# 1uO_c_v_1_2.net
KiCad netlist of a schematic drawn in EAGLE
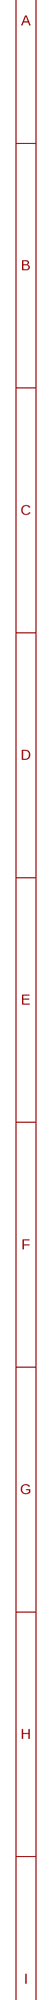
[diagram p0: schematic, sheet 1, part 1 of 2]
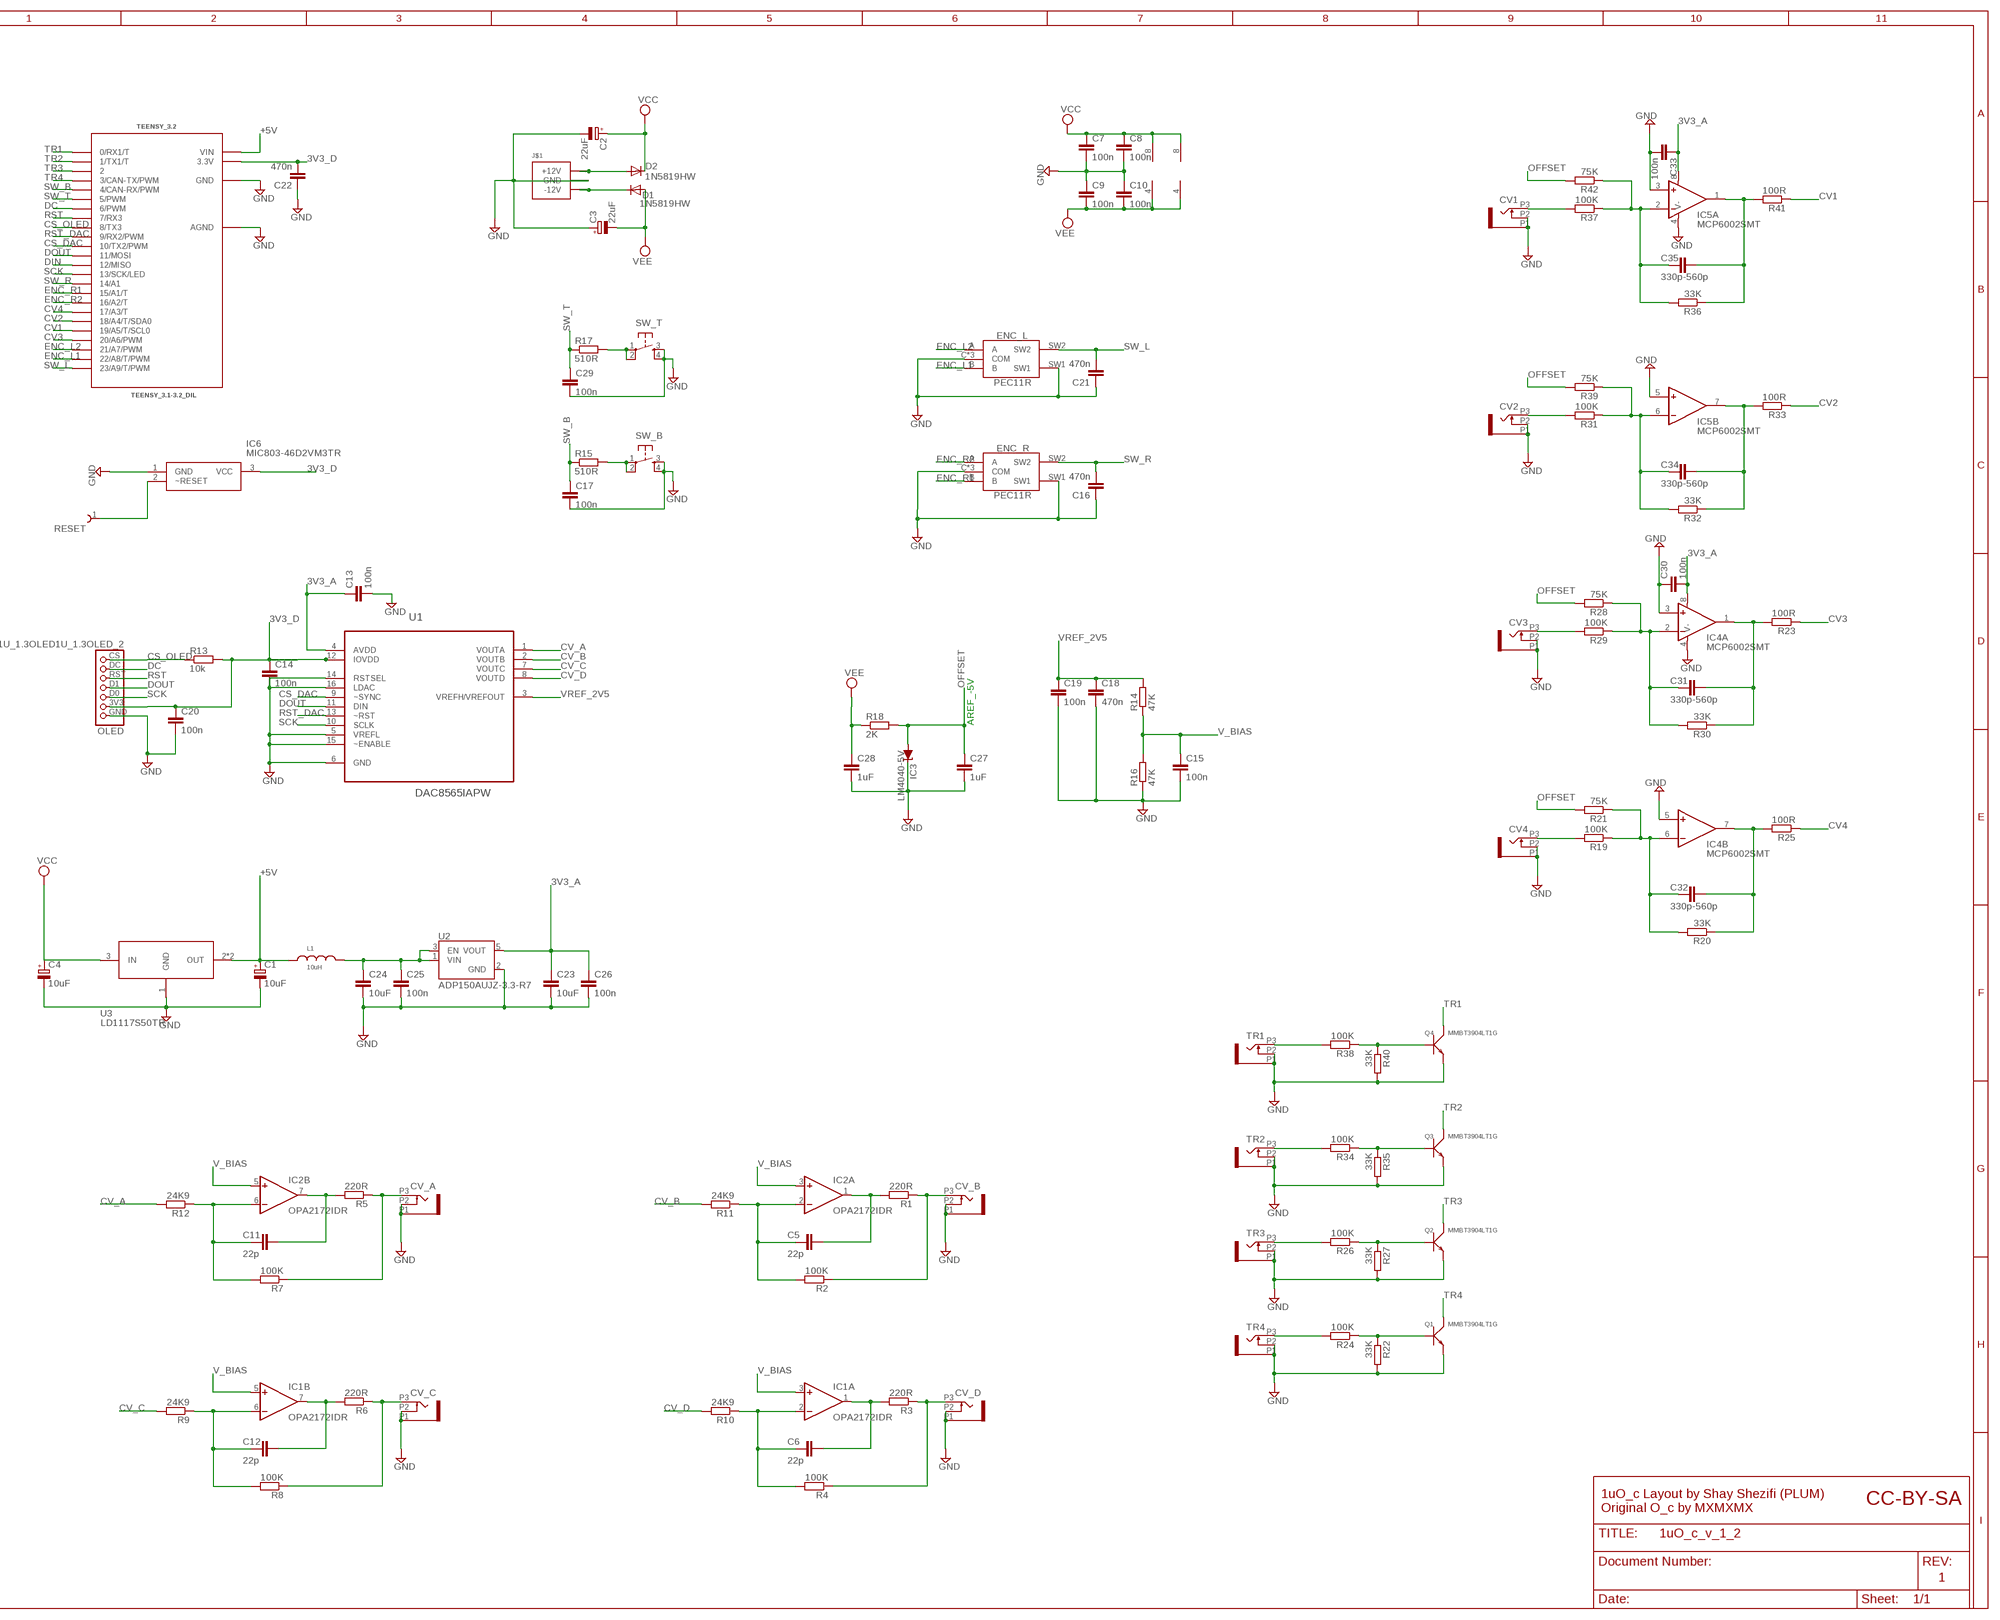
[diagram p1: schematic, sheet 1, part 2 of 2]

(export (version "E")
  (design (tool "Eeschema 10.0.6"))
  (components
    (comp (ref "C1")
      (value "10uF")
      (footprint "eagle-import:PANASONIC_B")
      (libsource (lib "eagle-import") (part "CPOL-EUB"))
    )
    (comp (ref "C2")
      (value "22uF")
      (footprint "eagle-import:PANASONIC_C")
      (libsource (lib "eagle-import") (part "CPOL-EUC"))
    )
    (comp (ref "C3")
      (value "22uF")
      (footprint "eagle-import:PANASONIC_C")
      (libsource (lib "eagle-import") (part "CPOL-EUC"))
    )
    (comp (ref "C4")
      (value "10uF")
      (footprint "eagle-import:PANASONIC_B")
      (libsource (lib "eagle-import") (part "CPOL-EUB"))
    )
    (comp (ref "C5")
      (value "22p")
      (footprint "eagle-import:C0603")
      (libsource (lib "eagle-import") (part "C-EUC0603"))
    )
    (comp (ref "C6")
      (value "22p")
      (footprint "eagle-import:C0603")
      (libsource (lib "eagle-import") (part "C-EUC0603"))
    )
    (comp (ref "C7")
      (value "100n")
      (footprint "eagle-import:C0603")
      (libsource (lib "eagle-import") (part "C-EUC0603"))
    )
    (comp (ref "C8")
      (value "100n")
      (footprint "eagle-import:C0603")
      (libsource (lib "eagle-import") (part "C-EUC0603"))
    )
    (comp (ref "C9")
      (value "100n")
      (footprint "eagle-import:C0603")
      (libsource (lib "eagle-import") (part "C-EUC0603"))
    )
    (comp (ref "C10")
      (value "100n")
      (footprint "eagle-import:C0603")
      (libsource (lib "eagle-import") (part "C-EUC0603"))
    )
    (comp (ref "C11")
      (value "22p")
      (footprint "eagle-import:C0603")
      (libsource (lib "eagle-import") (part "C-EUC0603"))
    )
    (comp (ref "C12")
      (value "22p")
      (footprint "eagle-import:C0603")
      (libsource (lib "eagle-import") (part "C-EUC0603"))
    )
    (comp (ref "C13")
      (value "100n")
      (footprint "eagle-import:C0603")
      (libsource (lib "eagle-import") (part "C-EUC0603"))
    )
    (comp (ref "C14")
      (value "100n")
      (footprint "eagle-import:C0603")
      (libsource (lib "eagle-import") (part "C-EUC0603"))
    )
    (comp (ref "C15")
      (value "100n")
      (footprint "eagle-import:C0603")
      (libsource (lib "eagle-import") (part "C-EUC0603"))
    )
    (comp (ref "C16")
      (value "470n")
      (footprint "eagle-import:C0603")
      (libsource (lib "eagle-import") (part "C-EUC0603"))
    )
    (comp (ref "C17")
      (value "100n")
      (footprint "eagle-import:C0603")
      (libsource (lib "eagle-import") (part "C-EUC0603"))
    )
    (comp (ref "C18")
      (value "470n")
      (footprint "eagle-import:C0603")
      (libsource (lib "eagle-import") (part "C-EUC0603"))
    )
    (comp (ref "C19")
      (value "100n")
      (footprint "eagle-import:C0603")
      (libsource (lib "eagle-import") (part "C-EUC0603"))
    )
    (comp (ref "C20")
      (value "100n")
      (footprint "eagle-import:C0603")
      (libsource (lib "eagle-import") (part "C-EUC0603"))
    )
    (comp (ref "C21")
      (value "470n")
      (footprint "eagle-import:C0603")
      (libsource (lib "eagle-import") (part "C-EUC0603"))
    )
    (comp (ref "C22")
      (value "470n")
      (footprint "eagle-import:C0603")
      (libsource (lib "eagle-import") (part "C-EUC0603"))
    )
    (comp (ref "C23")
      (value "10uF")
      (footprint "eagle-import:C1206K")
      (libsource (lib "eagle-import") (part "C-EUC1206K"))
    )
    (comp (ref "C24")
      (value "10uF")
      (footprint "eagle-import:C1206K")
      (libsource (lib "eagle-import") (part "C-EUC1206K"))
    )
    (comp (ref "C25")
      (value "100n")
      (footprint "eagle-import:C0603")
      (libsource (lib "eagle-import") (part "C-EUC0603"))
    )
    (comp (ref "C26")
      (value "100n")
      (footprint "eagle-import:C0603")
      (libsource (lib "eagle-import") (part "C-EUC0603"))
    )
    (comp (ref "C27")
      (value "1uF")
      (footprint "eagle-import:C0603")
      (libsource (lib "eagle-import") (part "C-EUC0603"))
    )
    (comp (ref "C28")
      (value "1uF")
      (footprint "eagle-import:C0603")
      (libsource (lib "eagle-import") (part "C-EUC0603"))
    )
    (comp (ref "C29")
      (value "100n")
      (footprint "eagle-import:C0603")
      (libsource (lib "eagle-import") (part "C-EUC0603"))
    )
    (comp (ref "C30")
      (value "100n")
      (footprint "eagle-import:C0603")
      (libsource (lib "eagle-import") (part "C-EUC0603"))
    )
    (comp (ref "C31")
      (value "330p-560p")
      (footprint "eagle-import:C0603")
      (libsource (lib "eagle-import") (part "C-EUC0603"))
    )
    (comp (ref "C32")
      (value "330p-560p")
      (footprint "eagle-import:C0603")
      (libsource (lib "eagle-import") (part "C-EUC0603"))
    )
    (comp (ref "C33")
      (value "100n")
      (footprint "eagle-import:C0603")
      (libsource (lib "eagle-import") (part "C-EUC0603"))
    )
    (comp (ref "C34")
      (value "330p-560p")
      (footprint "eagle-import:C0603")
      (libsource (lib "eagle-import") (part "C-EUC0603"))
    )
    (comp (ref "C35")
      (value "330p-560p")
      (footprint "eagle-import:C0603")
      (libsource (lib "eagle-import") (part "C-EUC0603"))
    )
    (comp (ref "CV1")
      (value "OG-PJ301_PJ301_THONKICONN")
      (footprint "eagle-import:OG-PJ301_WQP_PJ_301M6_NO_HOLE")
      (libsource (lib "eagle-import") (part "OG-PJ301_PJ301_THONKICONN"))
    )
    (comp (ref "CV2")
      (value "OG-PJ301_PJ301_THONKICONN")
      (footprint "eagle-import:OG-PJ301_WQP_PJ_301M6_NO_HOLE")
      (libsource (lib "eagle-import") (part "OG-PJ301_PJ301_THONKICONN"))
    )
    (comp (ref "CV3")
      (value "OG-PJ301_PJ301_THONKICONN")
      (footprint "eagle-import:OG-PJ301_WQP_PJ_301M6_NO_HOLE")
      (libsource (lib "eagle-import") (part "OG-PJ301_PJ301_THONKICONN"))
    )
    (comp (ref "CV4")
      (value "OG-PJ301_PJ301_THONKICONN")
      (footprint "eagle-import:OG-PJ301_WQP_PJ_301M6_NO_HOLE")
      (libsource (lib "eagle-import") (part "OG-PJ301_PJ301_THONKICONN"))
    )
    (comp (ref "CV_A")
      (value "OG-PJ301_PJ301_THONKICONN")
      (footprint "eagle-import:OG-PJ301_WQP_PJ_301M6_NO_HOLE")
      (libsource (lib "eagle-import") (part "OG-PJ301_PJ301_THONKICONN"))
    )
    (comp (ref "CV_B")
      (value "OG-PJ301_PJ301_THONKICONN")
      (footprint "eagle-import:OG-PJ301_WQP_PJ_301M6_NO_HOLE")
      (libsource (lib "eagle-import") (part "OG-PJ301_PJ301_THONKICONN"))
    )
    (comp (ref "CV_C")
      (value "OG-PJ301_PJ301_THONKICONN")
      (footprint "eagle-import:OG-PJ301_WQP_PJ_301M6_NO_HOLE")
      (libsource (lib "eagle-import") (part "OG-PJ301_PJ301_THONKICONN"))
    )
    (comp (ref "CV_D")
      (value "OG-PJ301_PJ301_THONKICONN")
      (footprint "eagle-import:OG-PJ301_WQP_PJ_301M6_NO_HOLE")
      (libsource (lib "eagle-import") (part "OG-PJ301_PJ301_THONKICONN"))
    )
    (comp (ref "D1")
      (value "1N5819HW")
      (footprint "eagle-import:DIODE_SOD123")
      (libsource (lib "eagle-import") (part "DIODE_DIODE-SOD123"))
    )
    (comp (ref "D2")
      (value "1N5819HW")
      (footprint "eagle-import:DIODE_SOD123")
      (libsource (lib "eagle-import") (part "DIODE_DIODE-SOD123"))
    )
    (comp (ref "ENC_L")
      (value "PEC11R")
      (footprint "eagle-import:PEC11R-4XXXK-SXXXX")
      (fields
        (field (name "ARROW_PART_NUMBER") "PEC11R-4215K-S0024")
        (field (name "RS_PART_NUMBER") "1674651")
      )
      (libsource (lib "eagle-import") (part "PEC11R"))
    )
    (comp (ref "ENC_R")
      (value "PEC11R")
      (footprint "eagle-import:PEC11R-4XXXK-SXXXX")
      (fields
        (field (name "ARROW_PART_NUMBER") "PEC11R-4215K-S0024")
        (field (name "RS_PART_NUMBER") "1674651")
      )
      (libsource (lib "eagle-import") (part "PEC11R"))
    )
    (comp (ref "IC1")
      (value "OPA2172IDR")
      (footprint "eagle-import:SO08")
      (libsource (lib "eagle-import") (part "TL072D"))
    )
    (comp (ref "IC2")
      (value "OPA2172IDR")
      (footprint "eagle-import:SO08")
      (libsource (lib "eagle-import") (part "TL072D"))
    )
    (comp (ref "IC3")
      (value "LM4040-5V")
      (footprint "eagle-import:DBZ_R-PDSO-G3")
      (libsource (lib "eagle-import") (part "LM4041DBZB12"))
    )
    (comp (ref "IC4")
      (value "MCP6002SMT")
      (footprint "eagle-import:SOIC8")
      (libsource (lib "eagle-import") (part "MCP6002SMT"))
    )
    (comp (ref "IC5")
      (value "MCP6002SMT")
      (footprint "eagle-import:SOIC8")
      (libsource (lib "eagle-import") (part "MCP6002SMT"))
    )
    (comp (ref "IC6")
      (value "MIC803-46D2VM3TR")
      (footprint "eagle-import:SOT95P230X110-3N")
      (libsource (lib "eagle-import") (part "MIC803-46D2VM3TR"))
    )
    (comp (ref "J$1")
      (value "POWER_SIMPLE10")
      (footprint "eagle-import:POWER_10")
      (libsource (lib "eagle-import") (part "POWER_SIMPLE10"))
    )
    (comp (ref "L1")
      (value "10uH")
      (footprint "eagle-import:WE-LQ_M")
      (libsource (lib "eagle-import") (part "WE-LQ_1210_744032001"))
    )
    (comp (ref "OLED")
      (value "1U_1.3OLED1U_1.3OLED_2")
      (footprint "eagle-import:1U_1.3OLED_2")
      (libsource (lib "eagle-import") (part "1U_1.3OLED1U_1.3OLED_2"))
    )
    (comp (ref "Q1")
      (value "MMBT3904LT1G")
      (footprint "eagle-import:SOT-23")
      (libsource (lib "eagle-import") (part "SMD-TRANSISTORS-NPN-40V-200MA-MMBT3904LT1G(SOT-23)"))
    )
    (comp (ref "Q2")
      (value "MMBT3904LT1G")
      (footprint "eagle-import:SOT-23")
      (libsource (lib "eagle-import") (part "SMD-TRANSISTORS-NPN-40V-200MA-MMBT3904LT1G(SOT-23)"))
    )
    (comp (ref "Q3")
      (value "MMBT3904LT1G")
      (footprint "eagle-import:SOT-23")
      (libsource (lib "eagle-import") (part "SMD-TRANSISTORS-NPN-40V-200MA-MMBT3904LT1G(SOT-23)"))
    )
    (comp (ref "Q4")
      (value "MMBT3904LT1G")
      (footprint "eagle-import:SOT-23")
      (libsource (lib "eagle-import") (part "SMD-TRANSISTORS-NPN-40V-200MA-MMBT3904LT1G(SOT-23)"))
    )
    (comp (ref "R1")
      (value "220R")
      (footprint "eagle-import:R0603")
      (libsource (lib "eagle-import") (part "R-EU_R0603"))
    )
    (comp (ref "R2")
      (value "100K")
      (footprint "eagle-import:R0603")
      (libsource (lib "eagle-import") (part "R-EU_R0603"))
    )
    (comp (ref "R3")
      (value "220R")
      (footprint "eagle-import:R0603")
      (libsource (lib "eagle-import") (part "R-EU_R0603"))
    )
    (comp (ref "R4")
      (value "100K")
      (footprint "eagle-import:R0603")
      (libsource (lib "eagle-import") (part "R-EU_R0603"))
    )
    (comp (ref "R5")
      (value "220R")
      (footprint "eagle-import:R0603")
      (libsource (lib "eagle-import") (part "R-EU_R0603"))
    )
    (comp (ref "R6")
      (value "220R")
      (footprint "eagle-import:R0603")
      (libsource (lib "eagle-import") (part "R-EU_R0603"))
    )
    (comp (ref "R7")
      (value "100K")
      (footprint "eagle-import:R0603")
      (libsource (lib "eagle-import") (part "R-EU_R0603"))
    )
    (comp (ref "R8")
      (value "100K")
      (footprint "eagle-import:R0603")
      (libsource (lib "eagle-import") (part "R-EU_R0603"))
    )
    (comp (ref "R9")
      (value "24K9")
      (footprint "eagle-import:R0603")
      (libsource (lib "eagle-import") (part "R-EU_R0603"))
    )
    (comp (ref "R10")
      (value "24K9")
      (footprint "eagle-import:R0603")
      (libsource (lib "eagle-import") (part "R-EU_R0603"))
    )
    (comp (ref "R11")
      (value "24K9")
      (footprint "eagle-import:R0603")
      (libsource (lib "eagle-import") (part "R-EU_R0603"))
    )
    (comp (ref "R12")
      (value "24K9")
      (footprint "eagle-import:R0603")
      (libsource (lib "eagle-import") (part "R-EU_R0603"))
    )
    (comp (ref "R13")
      (value "10k")
      (footprint "eagle-import:R0603")
      (libsource (lib "eagle-import") (part "R-EU_R0603"))
    )
    (comp (ref "R14")
      (value "47K")
      (footprint "eagle-import:R0603")
      (libsource (lib "eagle-import") (part "R-EU_R0603"))
    )
    (comp (ref "R15")
      (value "510R")
      (footprint "eagle-import:R0603")
      (libsource (lib "eagle-import") (part "R-EU_R0603"))
    )
    (comp (ref "R16")
      (value "47K")
      (footprint "eagle-import:R0603")
      (libsource (lib "eagle-import") (part "R-EU_R0603"))
    )
    (comp (ref "R17")
      (value "510R")
      (footprint "eagle-import:R0603")
      (libsource (lib "eagle-import") (part "R-EU_R0603"))
    )
    (comp (ref "R18")
      (value "2K")
      (footprint "eagle-import:R0603")
      (libsource (lib "eagle-import") (part "R-EU_R0603"))
    )
    (comp (ref "R19")
      (value "100K")
      (footprint "eagle-import:R0603")
      (libsource (lib "eagle-import") (part "R-EU_R0603"))
    )
    (comp (ref "R20")
      (value "33K")
      (footprint "eagle-import:R0603")
      (libsource (lib "eagle-import") (part "R-EU_R0603"))
    )
    (comp (ref "R21")
      (value "75K")
      (footprint "eagle-import:R0603")
      (libsource (lib "eagle-import") (part "R-EU_R0603"))
    )
    (comp (ref "R22")
      (value "33K")
      (footprint "eagle-import:R0603")
      (libsource (lib "eagle-import") (part "R-EU_R0603"))
    )
    (comp (ref "R23")
      (value "100R")
      (footprint "eagle-import:R0603")
      (libsource (lib "eagle-import") (part "R-EU_R0603"))
    )
    (comp (ref "R24")
      (value "100K")
      (footprint "eagle-import:R0603")
      (libsource (lib "eagle-import") (part "R-EU_R0603"))
    )
    (comp (ref "R25")
      (value "100R")
      (footprint "eagle-import:R0603")
      (libsource (lib "eagle-import") (part "R-EU_R0603"))
    )
    (comp (ref "R26")
      (value "100K")
      (footprint "eagle-import:R0603")
      (libsource (lib "eagle-import") (part "R-EU_R0603"))
    )
    (comp (ref "R27")
      (value "33K")
      (footprint "eagle-import:R0603")
      (libsource (lib "eagle-import") (part "R-EU_R0603"))
    )
    (comp (ref "R28")
      (value "75K")
      (footprint "eagle-import:R0603")
      (libsource (lib "eagle-import") (part "R-EU_R0603"))
    )
    (comp (ref "R29")
      (value "100K")
      (footprint "eagle-import:R0603")
      (libsource (lib "eagle-import") (part "R-EU_R0603"))
    )
    (comp (ref "R30")
      (value "33K")
      (footprint "eagle-import:R0603")
      (libsource (lib "eagle-import") (part "R-EU_R0603"))
    )
    (comp (ref "R31")
      (value "100K")
      (footprint "eagle-import:R0603")
      (libsource (lib "eagle-import") (part "R-EU_R0603"))
    )
    (comp (ref "R32")
      (value "33K")
      (footprint "eagle-import:R0603")
      (libsource (lib "eagle-import") (part "R-EU_R0603"))
    )
    (comp (ref "R33")
      (value "100R")
      (footprint "eagle-import:R0603")
      (libsource (lib "eagle-import") (part "R-EU_R0603"))
    )
    (comp (ref "R34")
      (value "100K")
      (footprint "eagle-import:R0603")
      (libsource (lib "eagle-import") (part "R-EU_R0603"))
    )
    (comp (ref "R35")
      (value "33K")
      (footprint "eagle-import:R0603")
      (libsource (lib "eagle-import") (part "R-EU_R0603"))
    )
    (comp (ref "R36")
      (value "33K")
      (footprint "eagle-import:R0603")
      (libsource (lib "eagle-import") (part "R-EU_R0603"))
    )
    (comp (ref "R37")
      (value "100K")
      (footprint "eagle-import:R0603")
      (libsource (lib "eagle-import") (part "R-EU_R0603"))
    )
    (comp (ref "R38")
      (value "100K")
      (footprint "eagle-import:R0603")
      (libsource (lib "eagle-import") (part "R-EU_R0603"))
    )
    (comp (ref "R39")
      (value "75K")
      (footprint "eagle-import:R0603")
      (libsource (lib "eagle-import") (part "R-EU_R0603"))
    )
    (comp (ref "R40")
      (value "33K")
      (footprint "eagle-import:R0603")
      (libsource (lib "eagle-import") (part "R-EU_R0603"))
    )
    (comp (ref "R41")
      (value "100R")
      (footprint "eagle-import:R0603")
      (libsource (lib "eagle-import") (part "R-EU_R0603"))
    )
    (comp (ref "R42")
      (value "75K")
      (footprint "eagle-import:R0603")
      (libsource (lib "eagle-import") (part "R-EU_R0603"))
    )
    (comp (ref "RESET")
      (value "61300111121")
      (footprint "eagle-import:61300111121")
      (libsource (lib "eagle-import") (part "61300111121"))
    )
    (comp (ref "SW_B")
      (value "TAC_SWITCHPTH")
      (footprint "eagle-import:TACTILE-PTH")
      (libsource (lib "eagle-import") (part "TAC_SWITCHPTH"))
    )
    (comp (ref "SW_T")
      (value "TAC_SWITCHPTH")
      (footprint "eagle-import:TACTILE-PTH")
      (libsource (lib "eagle-import") (part "TAC_SWITCHPTH"))
    )
    (comp (ref "TEENSY_3.2")
      (value "TEENSY_3.1-3.2_DIL")
      (footprint "eagle-import:TEENSY_3.0-3.2&LC_DIL")
      (libsource (lib "eagle-import") (part "TEENSY_3.1-3.2_DIL"))
    )
    (comp (ref "TR1")
      (value "OG-PJ301_PJ301_THONKICONN")
      (footprint "eagle-import:OG-PJ301_WQP_PJ_301M6_NO_HOLE")
      (libsource (lib "eagle-import") (part "OG-PJ301_PJ301_THONKICONN"))
    )
    (comp (ref "TR2")
      (value "OG-PJ301_PJ301_THONKICONN")
      (footprint "eagle-import:OG-PJ301_WQP_PJ_301M6_NO_HOLE")
      (libsource (lib "eagle-import") (part "OG-PJ301_PJ301_THONKICONN"))
    )
    (comp (ref "TR3")
      (value "OG-PJ301_PJ301_THONKICONN")
      (footprint "eagle-import:OG-PJ301_WQP_PJ_301M6_NO_HOLE")
      (libsource (lib "eagle-import") (part "OG-PJ301_PJ301_THONKICONN"))
    )
    (comp (ref "TR4")
      (value "OG-PJ301_PJ301_THONKICONN")
      (footprint "eagle-import:OG-PJ301_WQP_PJ_301M6_NO_HOLE")
      (libsource (lib "eagle-import") (part "OG-PJ301_PJ301_THONKICONN"))
    )
    (comp (ref "U1")
      (value "DAC8565IAPW")
      (footprint "eagle-import:SOP65P640X120-16N")
      (fields (field (name "MF") "Texas Instruments"))
      (libsource (lib "eagle-import") (part "DAC8565IAPW"))
    )
    (comp (ref "U2")
      (value "ADP150AUJZ-3.3-R7")
      (footprint "eagle-import:SOT95P280X100-5N")
      (fields (field (name "MF") "Analog Devices") (field (name "MP") "ADP150AUJZ-2.0-R7"))
      (libsource (lib "eagle-import") (part "ADP150AUJZ-3.3-R7"))
    )
    (comp (ref "U3")
      (value "LD1117S50TR")
      (footprint "eagle-import:SOT223")
      (fields (field (name "MF") "STMicroelectronics"))
      (libsource (lib "eagle-import") (part "LD1117S50TR"))
    )
  )
  (nets
    (net (code "1") (name "/+5V") (class "Default")
      (node (ref "C1") (pin "+") (pinfunction "+_+") (pintype "passive"))
      (node (ref "L1") (pin "1") (pinfunction "1_1") (pintype "passive"))
      (node (ref "TEENSY_3.2") (pin "VIN") (pinfunction "VIN_VIN") (pintype "power_in"))
      (node (ref "U3") (pin "2") (pinfunction "OUT_2") (pintype "output"))
      (node (ref "U3") (pin "4") (pinfunction "OUT_4") (pintype "output"))
    )
    (net (code "2") (name "/3V3_A") (class "Default")
      (node (ref "C13") (pin "1") (pinfunction "1_1") (pintype "passive"))
      (node (ref "C23") (pin "1") (pinfunction "1_1") (pintype "passive"))
      (node (ref "C26") (pin "1") (pinfunction "1_1") (pintype "passive"))
      (node (ref "C30") (pin "2") (pinfunction "2_2") (pintype "passive"))
      (node (ref "C33") (pin "1") (pinfunction "1_1") (pintype "passive"))
      (node (ref "IC4") (pin "8") (pinfunction "V+_8") (pintype "power_in"))
      (node (ref "IC5") (pin "8") (pinfunction "V+_8") (pintype "power_in"))
      (node (ref "U1") (pin "4") (pinfunction "AVDD_4") (pintype "power_in"))
      (node (ref "U2") (pin "5") (pinfunction "VOUT_5") (pintype "output"))
    )
    (net (code "3") (name "/3V3_D") (class "Default")
      (node (ref "C14") (pin "1") (pinfunction "1_1") (pintype "passive"))
      (node (ref "C20") (pin "1") (pinfunction "1_1") (pintype "passive"))
      (node (ref "C22") (pin "2") (pinfunction "2_2") (pintype "passive"))
      (node (ref "IC6") (pin "3") (pinfunction "VCC_3") (pintype "bidirectional"))
      (node (ref "OLED") (pin "3V3") (pinfunction "3V3_3V3") (pintype "passive"))
      (node (ref "R13") (pin "2") (pinfunction "2_2") (pintype "passive"))
      (node (ref "TEENSY_3.2") (pin "3.3V") (pinfunction "3.3V_3.3V") (pintype "power_in"))
      (node (ref "U1") (pin "12") (pinfunction "IOVDD_12") (pintype "power_in"))
    )
    (net (code "4") (name "/CS_DAC") (class "Default")
      (node (ref "TEENSY_3.2") (pin "10") (pinfunction "10/TX2/PWM_10") (pintype "bidirectional"))
      (node (ref "U1") (pin "9") (pinfunction "~{SYNC}_9") (pintype "input"))
    )
    (net (code "5") (name "/CS_OLED") (class "Default")
      (node (ref "OLED") (pin "CS") (pinfunction "CS_CS") (pintype "passive"))
      (node (ref "R13") (pin "1") (pinfunction "1_1") (pintype "passive"))
      (node (ref "TEENSY_3.2") (pin "8") (pinfunction "8/TX3_8") (pintype "bidirectional"))
    )
    (net (code "6") (name "/CV1") (class "Default")
      (node (ref "R41") (pin "1") (pinfunction "1_1") (pintype "passive"))
      (node (ref "TEENSY_3.2") (pin "19/A5") (pinfunction "19/A5/T/SCL0_19/A5") (pintype "bidirectional"))
    )
    (net (code "7") (name "/CV2") (class "Default")
      (node (ref "R33") (pin "1") (pinfunction "1_1") (pintype "passive"))
      (node (ref "TEENSY_3.2") (pin "18/A4") (pinfunction "18/A4/T/SDA0_18/A4") (pintype "bidirectional"))
    )
    (net (code "8") (name "/CV3") (class "Default")
      (node (ref "R23") (pin "1") (pinfunction "1_1") (pintype "passive"))
      (node (ref "TEENSY_3.2") (pin "20/A6") (pinfunction "20/A6/PWM_20/A6") (pintype "bidirectional"))
    )
    (net (code "9") (name "/CV4") (class "Default")
      (node (ref "R25") (pin "1") (pinfunction "1_1") (pintype "passive"))
      (node (ref "TEENSY_3.2") (pin "17/A3") (pinfunction "17/A3/T_17/A3") (pintype "bidirectional"))
    )
    (net (code "10") (name "/CV_A") (class "Default")
      (node (ref "R12") (pin "2") (pinfunction "2_2") (pintype "passive"))
      (node (ref "U1") (pin "1") (pinfunction "VOUTA_1") (pintype "output"))
    )
    (net (code "11") (name "/CV_B") (class "Default")
      (node (ref "R11") (pin "2") (pinfunction "2_2") (pintype "passive"))
      (node (ref "U1") (pin "2") (pinfunction "VOUTB_2") (pintype "output"))
    )
    (net (code "12") (name "/CV_C") (class "Default")
      (node (ref "R9") (pin "2") (pinfunction "2_2") (pintype "passive"))
      (node (ref "U1") (pin "7") (pinfunction "VOUTC_7") (pintype "output"))
    )
    (net (code "13") (name "/CV_D") (class "Default")
      (node (ref "R10") (pin "2") (pinfunction "2_2") (pintype "passive"))
      (node (ref "U1") (pin "8") (pinfunction "VOUTD_8") (pintype "output"))
    )
    (net (code "14") (name "/DC") (class "Default")
      (node (ref "OLED") (pin "DC") (pinfunction "DC_DC") (pintype "passive"))
      (node (ref "TEENSY_3.2") (pin "6") (pinfunction "6/PWM_6") (pintype "bidirectional"))
    )
    (net (code "15") (name "/DIN") (class "Default")
      (node (ref "TEENSY_3.2") (pin "12") (pinfunction "12/MISO_12") (pintype "bidirectional"))
    )
    (net (code "16") (name "/DOUT") (class "Default")
      (node (ref "OLED") (pin "D1") (pinfunction "D1_D1") (pintype "passive"))
      (node (ref "TEENSY_3.2") (pin "11") (pinfunction "11/MOSI_11") (pintype "bidirectional"))
      (node (ref "U1") (pin "11") (pinfunction "DIN_11") (pintype "input"))
    )
    (net (code "17") (name "/ENC_L1") (class "Default")
      (node (ref "ENC_L") (pin "B") (pinfunction "B_B") (pintype "bidirectional"))
      (node (ref "TEENSY_3.2") (pin "22/A8") (pinfunction "22/A8/T/PWM_22/A8") (pintype "bidirectional"))
    )
    (net (code "18") (name "/ENC_L2") (class "Default")
      (node (ref "ENC_L") (pin "A") (pinfunction "A_A") (pintype "bidirectional"))
      (node (ref "TEENSY_3.2") (pin "21/A7") (pinfunction "21/A7/PWM_21/A7") (pintype "bidirectional"))
    )
    (net (code "19") (name "/ENC_R1") (class "Default")
      (node (ref "ENC_R") (pin "B") (pinfunction "B_B") (pintype "bidirectional"))
      (node (ref "TEENSY_3.2") (pin "15/A1") (pinfunction "15/A1/T_15/A1") (pintype "bidirectional"))
    )
    (net (code "20") (name "/ENC_R2") (class "Default")
      (node (ref "ENC_R") (pin "A") (pinfunction "A_A") (pintype "bidirectional"))
      (node (ref "TEENSY_3.2") (pin "16/A2") (pinfunction "16/A2/T_16/A2") (pintype "bidirectional"))
    )
    (net (code "21") (name "/OFFSET") (class "Default")
      (node (ref "C27") (pin "1") (pinfunction "1_1") (pintype "passive"))
      (node (ref "IC3") (pin "2") (pinfunction "A_2") (pintype "passive"))
      (node (ref "R18") (pin "2") (pinfunction "2_2") (pintype "passive"))
      (node (ref "R21") (pin "2") (pinfunction "2_2") (pintype "passive"))
      (node (ref "R28") (pin "2") (pinfunction "2_2") (pintype "passive"))
      (node (ref "R39") (pin "2") (pinfunction "2_2") (pintype "passive"))
      (node (ref "R42") (pin "2") (pinfunction "2_2") (pintype "passive"))
    )
    (net (code "22") (name "/RST") (class "Default")
      (node (ref "OLED") (pin "RST") (pinfunction "RST_RST") (pintype "passive"))
      (node (ref "TEENSY_3.2") (pin "7") (pinfunction "7/RX3_7") (pintype "bidirectional"))
    )
    (net (code "23") (name "/RST_DAC") (class "Default")
      (node (ref "TEENSY_3.2") (pin "9") (pinfunction "9/RX2/PWM_9") (pintype "bidirectional"))
      (node (ref "U1") (pin "13") (pinfunction "~{RST}_13") (pintype "input"))
    )
    (net (code "24") (name "/SCK") (class "Default")
      (node (ref "OLED") (pin "D0") (pinfunction "D0_D0") (pintype "passive"))
      (node (ref "TEENSY_3.2") (pin "13") (pinfunction "13/SCK/LED_13") (pintype "bidirectional"))
      (node (ref "U1") (pin "10") (pinfunction "SCLK_10") (pintype "input"))
    )
    (net (code "25") (name "/SW_B") (class "Default")
      (node (ref "C17") (pin "1") (pinfunction "1_1") (pintype "passive"))
      (node (ref "R15") (pin "1") (pinfunction "1_1") (pintype "passive"))
      (node (ref "TEENSY_3.2") (pin "4") (pinfunction "4/CAN-RX/PWM_4") (pintype "bidirectional"))
    )
    (net (code "26") (name "/SW_L") (class "Default")
      (node (ref "C21") (pin "2") (pinfunction "2_2") (pintype "passive"))
      (node (ref "ENC_L") (pin "SW2") (pinfunction "SW2_SW2") (pintype "bidirectional"))
      (node (ref "TEENSY_3.2") (pin "23/A9") (pinfunction "23/A9/T/PWM_23/A9") (pintype "bidirectional"))
    )
    (net (code "27") (name "/SW_R") (class "Default")
      (node (ref "C16") (pin "2") (pinfunction "2_2") (pintype "passive"))
      (node (ref "ENC_R") (pin "SW2") (pinfunction "SW2_SW2") (pintype "bidirectional"))
      (node (ref "TEENSY_3.2") (pin "14/A0") (pinfunction "14/A1_14/A0") (pintype "bidirectional"))
    )
    (net (code "28") (name "/SW_T") (class "Default")
      (node (ref "C29") (pin "1") (pinfunction "1_1") (pintype "passive"))
      (node (ref "R17") (pin "1") (pinfunction "1_1") (pintype "passive"))
      (node (ref "TEENSY_3.2") (pin "5") (pinfunction "5/PWM_5") (pintype "bidirectional"))
    )
    (net (code "29") (name "/TR1") (class "Default")
      (node (ref "Q4") (pin "3") (pinfunction "C_3") (pintype "passive"))
      (node (ref "TEENSY_3.2") (pin "0") (pinfunction "0/RX1/T_0") (pintype "bidirectional"))
    )
    (net (code "30") (name "/TR2") (class "Default")
      (node (ref "Q3") (pin "3") (pinfunction "C_3") (pintype "passive"))
      (node (ref "TEENSY_3.2") (pin "1") (pinfunction "1/TX1/T_1") (pintype "bidirectional"))
    )
    (net (code "31") (name "/TR3") (class "Default")
      (node (ref "Q2") (pin "3") (pinfunction "C_3") (pintype "passive"))
      (node (ref "TEENSY_3.2") (pin "2") (pinfunction "2_2") (pintype "bidirectional"))
    )
    (net (code "32") (name "/TR4") (class "Default")
      (node (ref "Q1") (pin "3") (pinfunction "C_3") (pintype "passive"))
      (node (ref "TEENSY_3.2") (pin "3") (pinfunction "3/CAN-TX/PWM_3") (pintype "bidirectional"))
    )
    (net (code "33") (name "/VREF_2V5") (class "Default")
      (node (ref "C18") (pin "1") (pinfunction "1_1") (pintype "passive"))
      (node (ref "C19") (pin "1") (pinfunction "1_1") (pintype "passive"))
      (node (ref "R14") (pin "2") (pinfunction "2_2") (pintype "passive"))
      (node (ref "U1") (pin "3") (pinfunction "VREFH/VREFOUT_3") (pintype "bidirectional"))
    )
    (net (code "34") (name "/V_BIAS") (class "Default")
      (node (ref "C15") (pin "1") (pinfunction "1_1") (pintype "passive"))
      (node (ref "IC1") (pin "3") (pinfunction "+IN_3") (pintype "input"))
      (node (ref "IC1") (pin "5") (pinfunction "+IN_5") (pintype "input"))
      (node (ref "IC2") (pin "3") (pinfunction "+IN_3") (pintype "input"))
      (node (ref "IC2") (pin "5") (pinfunction "+IN_5") (pintype "input"))
      (node (ref "R14") (pin "1") (pinfunction "1_1") (pintype "passive"))
      (node (ref "R16") (pin "2") (pinfunction "2_2") (pintype "passive"))
    )
    (net (code "35") (name "GND") (class "Default")
      (node (ref "C1") (pin "-") (pinfunction "-_-") (pintype "passive"))
      (node (ref "C10") (pin "1") (pinfunction "1_1") (pintype "passive"))
      (node (ref "C13") (pin "2") (pinfunction "2_2") (pintype "passive"))
      (node (ref "C14") (pin "2") (pinfunction "2_2") (pintype "passive"))
      (node (ref "C15") (pin "2") (pinfunction "2_2") (pintype "passive"))
      (node (ref "C16") (pin "1") (pinfunction "1_1") (pintype "passive"))
      (node (ref "C17") (pin "2") (pinfunction "2_2") (pintype "passive"))
      (node (ref "C18") (pin "2") (pinfunction "2_2") (pintype "passive"))
      (node (ref "C19") (pin "2") (pinfunction "2_2") (pintype "passive"))
      (node (ref "C2") (pin "-") (pinfunction "-_-") (pintype "passive"))
      (node (ref "C20") (pin "2") (pinfunction "2_2") (pintype "passive"))
      (node (ref "C21") (pin "1") (pinfunction "1_1") (pintype "passive"))
      (node (ref "C22") (pin "1") (pinfunction "1_1") (pintype "passive"))
      (node (ref "C23") (pin "2") (pinfunction "2_2") (pintype "passive"))
      (node (ref "C24") (pin "2") (pinfunction "2_2") (pintype "passive"))
      (node (ref "C25") (pin "2") (pinfunction "2_2") (pintype "passive"))
      (node (ref "C26") (pin "2") (pinfunction "2_2") (pintype "passive"))
      (node (ref "C27") (pin "2") (pinfunction "2_2") (pintype "passive"))
      (node (ref "C28") (pin "2") (pinfunction "2_2") (pintype "passive"))
      (node (ref "C29") (pin "2") (pinfunction "2_2") (pintype "passive"))
      (node (ref "C3") (pin "+") (pinfunction "+_+") (pintype "passive"))
      (node (ref "C30") (pin "1") (pinfunction "1_1") (pintype "passive"))
      (node (ref "C33") (pin "2") (pinfunction "2_2") (pintype "passive"))
      (node (ref "C4") (pin "-") (pinfunction "-_-") (pintype "passive"))
      (node (ref "C7") (pin "2") (pinfunction "2_2") (pintype "passive"))
      (node (ref "C8") (pin "2") (pinfunction "2_2") (pintype "passive"))
      (node (ref "C9") (pin "1") (pinfunction "1_1") (pintype "passive"))
      (node (ref "CV1") (pin "P1") (pinfunction "1_P1") (pintype "passive"))
      (node (ref "CV1") (pin "P2") (pinfunction "2_P2") (pintype "passive"))
      (node (ref "CV2") (pin "P1") (pinfunction "1_P1") (pintype "passive"))
      (node (ref "CV2") (pin "P2") (pinfunction "2_P2") (pintype "passive"))
      (node (ref "CV3") (pin "P1") (pinfunction "1_P1") (pintype "passive"))
      (node (ref "CV3") (pin "P2") (pinfunction "2_P2") (pintype "passive"))
      (node (ref "CV4") (pin "P1") (pinfunction "1_P1") (pintype "passive"))
      (node (ref "CV4") (pin "P2") (pinfunction "2_P2") (pintype "passive"))
      (node (ref "CV_A") (pin "P1") (pinfunction "1_P1") (pintype "passive"))
      (node (ref "CV_A") (pin "P2") (pinfunction "2_P2") (pintype "passive"))
      (node (ref "CV_B") (pin "P1") (pinfunction "1_P1") (pintype "passive"))
      (node (ref "CV_B") (pin "P2") (pinfunction "2_P2") (pintype "passive"))
      (node (ref "CV_C") (pin "P1") (pinfunction "1_P1") (pintype "passive"))
      (node (ref "CV_C") (pin "P2") (pinfunction "2_P2") (pintype "passive"))
      (node (ref "CV_D") (pin "P1") (pinfunction "1_P1") (pintype "passive"))
      (node (ref "CV_D") (pin "P2") (pinfunction "2_P2") (pintype "passive"))
      (node (ref "ENC_L") (pin "C") (pinfunction "COM_C") (pintype "bidirectional"))
      (node (ref "ENC_L") (pin "SH1") (pinfunction "COM_SH1") (pintype "bidirectional"))
      (node (ref "ENC_L") (pin "SH2") (pinfunction "COM_SH2") (pintype "bidirectional"))
      (node (ref "ENC_L") (pin "SW1") (pinfunction "SW1_SW1") (pintype "bidirectional"))
      (node (ref "ENC_R") (pin "C") (pinfunction "COM_C") (pintype "bidirectional"))
      (node (ref "ENC_R") (pin "SH1") (pinfunction "COM_SH1") (pintype "bidirectional"))
      (node (ref "ENC_R") (pin "SH2") (pinfunction "COM_SH2") (pintype "bidirectional"))
      (node (ref "ENC_R") (pin "SW1") (pinfunction "SW1_SW1") (pintype "bidirectional"))
      (node (ref "IC3") (pin "1") (pinfunction "C_1") (pintype "passive"))
      (node (ref "IC4") (pin "3") (pinfunction "+IN_3") (pintype "input"))
      (node (ref "IC4") (pin "4") (pinfunction "V-_4") (pintype "power_in"))
      (node (ref "IC4") (pin "5") (pinfunction "+IN_5") (pintype "input"))
      (node (ref "IC5") (pin "3") (pinfunction "+IN_3") (pintype "input"))
      (node (ref "IC5") (pin "4") (pinfunction "V-_4") (pintype "power_in"))
      (node (ref "IC5") (pin "5") (pinfunction "+IN_5") (pintype "input"))
      (node (ref "IC6") (pin "1") (pinfunction "GND_1") (pintype "bidirectional"))
      (node (ref "J$1") (pin "3") (pinfunction "GND_3") (pintype "bidirectional"))
      (node (ref "J$1") (pin "4") (pinfunction "GND_4") (pintype "bidirectional"))
      (node (ref "J$1") (pin "5") (pinfunction "GND_5") (pintype "bidirectional"))
      (node (ref "J$1") (pin "6") (pinfunction "GND_6") (pintype "bidirectional"))
      (node (ref "J$1") (pin "7") (pinfunction "GND_7") (pintype "bidirectional"))
      (node (ref "J$1") (pin "8") (pinfunction "GND_8") (pintype "bidirectional"))
      (node (ref "OLED") (pin "GND") (pinfunction "GND_GND") (pintype "passive"))
      (node (ref "Q1") (pin "2") (pinfunction "E_2") (pintype "passive"))
      (node (ref "Q2") (pin "2") (pinfunction "E_2") (pintype "passive"))
      (node (ref "Q3") (pin "2") (pinfunction "E_2") (pintype "passive"))
      (node (ref "Q4") (pin "2") (pinfunction "E_2") (pintype "passive"))
      (node (ref "R16") (pin "1") (pinfunction "1_1") (pintype "passive"))
      (node (ref "R22") (pin "2") (pinfunction "2_2") (pintype "passive"))
      (node (ref "R27") (pin "2") (pinfunction "2_2") (pintype "passive"))
      (node (ref "R35") (pin "2") (pinfunction "2_2") (pintype "passive"))
      (node (ref "R40") (pin "2") (pinfunction "2_2") (pintype "passive"))
      (node (ref "SW_B") (pin "3") (pinfunction "3_3") (pintype "passive"))
      (node (ref "SW_B") (pin "4") (pinfunction "4_4") (pintype "passive"))
      (node (ref "SW_T") (pin "3") (pinfunction "3_3") (pintype "passive"))
      (node (ref "SW_T") (pin "4") (pinfunction "4_4") (pintype "passive"))
      (node (ref "TEENSY_3.2") (pin "AGND") (pinfunction "AGND_AGND") (pintype "power_in"))
      (node (ref "TEENSY_3.2") (pin "GND") (pinfunction "GND_GND") (pintype "power_in"))
      (node (ref "TR1") (pin "P1") (pinfunction "1_P1") (pintype "passive"))
      (node (ref "TR1") (pin "P2") (pinfunction "2_P2") (pintype "passive"))
      (node (ref "TR2") (pin "P1") (pinfunction "1_P1") (pintype "passive"))
      (node (ref "TR2") (pin "P2") (pinfunction "2_P2") (pintype "passive"))
      (node (ref "TR3") (pin "P1") (pinfunction "1_P1") (pintype "passive"))
      (node (ref "TR3") (pin "P2") (pinfunction "2_P2") (pintype "passive"))
      (node (ref "TR4") (pin "P1") (pinfunction "1_P1") (pintype "passive"))
      (node (ref "TR4") (pin "P2") (pinfunction "2_P2") (pintype "passive"))
      (node (ref "U1") (pin "14") (pinfunction "RSTSEL_14") (pintype "input"))
      (node (ref "U1") (pin "15") (pinfunction "~{ENABLE}_15") (pintype "input"))
      (node (ref "U1") (pin "16") (pinfunction "LDAC_16") (pintype "input"))
      (node (ref "U1") (pin "5") (pinfunction "VREFL_5") (pintype "input"))
      (node (ref "U1") (pin "6") (pinfunction "GND_6") (pintype "passive"))
      (node (ref "U2") (pin "2") (pinfunction "GND_2") (pintype "power_in"))
      (node (ref "U3") (pin "1") (pinfunction "GND_1") (pintype "passive"))
    )
    (net (code "36") (name "Net-(CV1-3)") (class "Default")
      (node (ref "CV1") (pin "P3") (pinfunction "3_P3") (pintype "passive"))
      (node (ref "R37") (pin "2") (pinfunction "2_2") (pintype "passive"))
    )
    (net (code "37") (name "Net-(CV2-3)") (class "Default")
      (node (ref "CV2") (pin "P3") (pinfunction "3_P3") (pintype "passive"))
      (node (ref "R31") (pin "2") (pinfunction "2_2") (pintype "passive"))
    )
    (net (code "38") (name "Net-(CV3-3)") (class "Default")
      (node (ref "CV3") (pin "P3") (pinfunction "3_P3") (pintype "passive"))
      (node (ref "R29") (pin "2") (pinfunction "2_2") (pintype "passive"))
    )
    (net (code "39") (name "Net-(CV4-3)") (class "Default")
      (node (ref "CV4") (pin "P3") (pinfunction "3_P3") (pintype "passive"))
      (node (ref "R19") (pin "2") (pinfunction "2_2") (pintype "passive"))
    )
    (net (code "40") (name "Net-(CV_A-3)") (class "Default")
      (node (ref "CV_A") (pin "P3") (pinfunction "3_P3") (pintype "passive"))
      (node (ref "R5") (pin "1") (pinfunction "1_1") (pintype "passive"))
      (node (ref "R7") (pin "1") (pinfunction "1_1") (pintype "passive"))
    )
    (net (code "41") (name "Net-(CV_B-3)") (class "Default")
      (node (ref "CV_B") (pin "P3") (pinfunction "3_P3") (pintype "passive"))
      (node (ref "R1") (pin "1") (pinfunction "1_1") (pintype "passive"))
      (node (ref "R2") (pin "1") (pinfunction "1_1") (pintype "passive"))
    )
    (net (code "42") (name "Net-(CV_C-3)") (class "Default")
      (node (ref "CV_C") (pin "P3") (pinfunction "3_P3") (pintype "passive"))
      (node (ref "R6") (pin "1") (pinfunction "1_1") (pintype "passive"))
      (node (ref "R8") (pin "1") (pinfunction "1_1") (pintype "passive"))
    )
    (net (code "43") (name "Net-(CV_D-3)") (class "Default")
      (node (ref "CV_D") (pin "P3") (pinfunction "3_P3") (pintype "passive"))
      (node (ref "R3") (pin "1") (pinfunction "1_1") (pintype "passive"))
      (node (ref "R4") (pin "1") (pinfunction "1_1") (pintype "passive"))
    )
    (net (code "44") (name "Net-(D1-PadC)") (class "Default")
      (node (ref "D1") (pin "C") (pinfunction "C_C") (pintype "passive"))
      (node (ref "J$1") (pin "1") (pinfunction "-12V_1") (pintype "bidirectional"))
      (node (ref "J$1") (pin "2") (pinfunction "-12V_2") (pintype "bidirectional"))
    )
    (net (code "45") (name "Net-(D2-PadA)") (class "Default")
      (node (ref "D2") (pin "A") (pinfunction "A_A") (pintype "passive"))
      (node (ref "J$1") (pin "10") (pinfunction "+12V_10") (pintype "bidirectional"))
      (node (ref "J$1") (pin "9") (pinfunction "+12V_9") (pintype "bidirectional"))
    )
    (net (code "46") (name "Net-(IC1A--IN)") (class "Default")
      (node (ref "C6") (pin "2") (pinfunction "2_2") (pintype "passive"))
      (node (ref "IC1") (pin "2") (pinfunction "-IN_2") (pintype "input"))
      (node (ref "R10") (pin "1") (pinfunction "1_1") (pintype "passive"))
      (node (ref "R4") (pin "2") (pinfunction "2_2") (pintype "passive"))
    )
    (net (code "47") (name "Net-(IC1A-OUT)") (class "Default")
      (node (ref "C6") (pin "1") (pinfunction "1_1") (pintype "passive"))
      (node (ref "IC1") (pin "1") (pinfunction "OUT_1") (pintype "output"))
      (node (ref "R3") (pin "2") (pinfunction "2_2") (pintype "passive"))
    )
    (net (code "48") (name "Net-(IC1B--IN)") (class "Default")
      (node (ref "C12") (pin "2") (pinfunction "2_2") (pintype "passive"))
      (node (ref "IC1") (pin "6") (pinfunction "-IN_6") (pintype "input"))
      (node (ref "R8") (pin "2") (pinfunction "2_2") (pintype "passive"))
      (node (ref "R9") (pin "1") (pinfunction "1_1") (pintype "passive"))
    )
    (net (code "49") (name "Net-(IC1B-OUT)") (class "Default")
      (node (ref "C12") (pin "1") (pinfunction "1_1") (pintype "passive"))
      (node (ref "IC1") (pin "7") (pinfunction "OUT_7") (pintype "output"))
      (node (ref "R6") (pin "2") (pinfunction "2_2") (pintype "passive"))
    )
    (net (code "50") (name "Net-(IC2A--IN)") (class "Default")
      (node (ref "C5") (pin "2") (pinfunction "2_2") (pintype "passive"))
      (node (ref "IC2") (pin "2") (pinfunction "-IN_2") (pintype "input"))
      (node (ref "R11") (pin "1") (pinfunction "1_1") (pintype "passive"))
      (node (ref "R2") (pin "2") (pinfunction "2_2") (pintype "passive"))
    )
    (net (code "51") (name "Net-(IC2A-OUT)") (class "Default")
      (node (ref "C5") (pin "1") (pinfunction "1_1") (pintype "passive"))
      (node (ref "IC2") (pin "1") (pinfunction "OUT_1") (pintype "output"))
      (node (ref "R1") (pin "2") (pinfunction "2_2") (pintype "passive"))
    )
    (net (code "52") (name "Net-(IC2B--IN)") (class "Default")
      (node (ref "C11") (pin "2") (pinfunction "2_2") (pintype "passive"))
      (node (ref "IC2") (pin "6") (pinfunction "-IN_6") (pintype "input"))
      (node (ref "R12") (pin "1") (pinfunction "1_1") (pintype "passive"))
      (node (ref "R7") (pin "2") (pinfunction "2_2") (pintype "passive"))
    )
    (net (code "53") (name "Net-(IC2B-OUT)") (class "Default")
      (node (ref "C11") (pin "1") (pinfunction "1_1") (pintype "passive"))
      (node (ref "IC2") (pin "7") (pinfunction "OUT_7") (pintype "output"))
      (node (ref "R5") (pin "2") (pinfunction "2_2") (pintype "passive"))
    )
    (net (code "54") (name "Net-(IC4A--IN)") (class "Default")
      (node (ref "C31") (pin "2") (pinfunction "2_2") (pintype "passive"))
      (node (ref "IC4") (pin "2") (pinfunction "-IN_2") (pintype "input"))
      (node (ref "R28") (pin "1") (pinfunction "1_1") (pintype "passive"))
      (node (ref "R29") (pin "1") (pinfunction "1_1") (pintype "passive"))
      (node (ref "R30") (pin "2") (pinfunction "2_2") (pintype "passive"))
    )
    (net (code "55") (name "Net-(IC4A-OUT)") (class "Default")
      (node (ref "C31") (pin "1") (pinfunction "1_1") (pintype "passive"))
      (node (ref "IC4") (pin "1") (pinfunction "OUT_1") (pintype "output"))
      (node (ref "R23") (pin "2") (pinfunction "2_2") (pintype "passive"))
      (node (ref "R30") (pin "1") (pinfunction "1_1") (pintype "passive"))
    )
    (net (code "56") (name "Net-(IC4B--IN)") (class "Default")
      (node (ref "C32") (pin "2") (pinfunction "2_2") (pintype "passive"))
      (node (ref "IC4") (pin "6") (pinfunction "-IN_6") (pintype "input"))
      (node (ref "R19") (pin "1") (pinfunction "1_1") (pintype "passive"))
      (node (ref "R20") (pin "2") (pinfunction "2_2") (pintype "passive"))
      (node (ref "R21") (pin "1") (pinfunction "1_1") (pintype "passive"))
    )
    (net (code "57") (name "Net-(IC4B-OUT)") (class "Default")
      (node (ref "C32") (pin "1") (pinfunction "1_1") (pintype "passive"))
      (node (ref "IC4") (pin "7") (pinfunction "OUT_7") (pintype "output"))
      (node (ref "R20") (pin "1") (pinfunction "1_1") (pintype "passive"))
      (node (ref "R25") (pin "2") (pinfunction "2_2") (pintype "passive"))
    )
    (net (code "58") (name "Net-(IC5A--IN)") (class "Default")
      (node (ref "C35") (pin "2") (pinfunction "2_2") (pintype "passive"))
      (node (ref "IC5") (pin "2") (pinfunction "-IN_2") (pintype "input"))
      (node (ref "R36") (pin "2") (pinfunction "2_2") (pintype "passive"))
      (node (ref "R37") (pin "1") (pinfunction "1_1") (pintype "passive"))
      (node (ref "R42") (pin "1") (pinfunction "1_1") (pintype "passive"))
    )
    (net (code "59") (name "Net-(IC5A-OUT)") (class "Default")
      (node (ref "C35") (pin "1") (pinfunction "1_1") (pintype "passive"))
      (node (ref "IC5") (pin "1") (pinfunction "OUT_1") (pintype "output"))
      (node (ref "R36") (pin "1") (pinfunction "1_1") (pintype "passive"))
      (node (ref "R41") (pin "2") (pinfunction "2_2") (pintype "passive"))
    )
    (net (code "60") (name "Net-(IC5B--IN)") (class "Default")
      (node (ref "C34") (pin "2") (pinfunction "2_2") (pintype "passive"))
      (node (ref "IC5") (pin "6") (pinfunction "-IN_6") (pintype "input"))
      (node (ref "R31") (pin "1") (pinfunction "1_1") (pintype "passive"))
      (node (ref "R32") (pin "2") (pinfunction "2_2") (pintype "passive"))
      (node (ref "R39") (pin "1") (pinfunction "1_1") (pintype "passive"))
    )
    (net (code "61") (name "Net-(IC5B-OUT)") (class "Default")
      (node (ref "C34") (pin "1") (pinfunction "1_1") (pintype "passive"))
      (node (ref "IC5") (pin "7") (pinfunction "OUT_7") (pintype "output"))
      (node (ref "R32") (pin "1") (pinfunction "1_1") (pintype "passive"))
      (node (ref "R33") (pin "2") (pinfunction "2_2") (pintype "passive"))
    )
    (net (code "62") (name "Net-(IC6-~{RESET})") (class "Default")
      (node (ref "IC6") (pin "2") (pinfunction "~{RESET}_2") (pintype "bidirectional"))
      (node (ref "RESET") (pin "1") (pinfunction "1_1") (pintype "passive"))
    )
    (net (code "63") (name "Net-(Q1-B)") (class "Default")
      (node (ref "Q1") (pin "1") (pinfunction "B_1") (pintype "passive"))
      (node (ref "R22") (pin "1") (pinfunction "1_1") (pintype "passive"))
      (node (ref "R24") (pin "1") (pinfunction "1_1") (pintype "passive"))
    )
    (net (code "64") (name "Net-(Q2-B)") (class "Default")
      (node (ref "Q2") (pin "1") (pinfunction "B_1") (pintype "passive"))
      (node (ref "R26") (pin "1") (pinfunction "1_1") (pintype "passive"))
      (node (ref "R27") (pin "1") (pinfunction "1_1") (pintype "passive"))
    )
    (net (code "65") (name "Net-(Q3-B)") (class "Default")
      (node (ref "Q3") (pin "1") (pinfunction "B_1") (pintype "passive"))
      (node (ref "R34") (pin "1") (pinfunction "1_1") (pintype "passive"))
      (node (ref "R35") (pin "1") (pinfunction "1_1") (pintype "passive"))
    )
    (net (code "66") (name "Net-(Q4-B)") (class "Default")
      (node (ref "Q4") (pin "1") (pinfunction "B_1") (pintype "passive"))
      (node (ref "R38") (pin "1") (pinfunction "1_1") (pintype "passive"))
      (node (ref "R40") (pin "1") (pinfunction "1_1") (pintype "passive"))
    )
    (net (code "67") (name "Net-(R15-Pad2)") (class "Default")
      (node (ref "R15") (pin "2") (pinfunction "2_2") (pintype "passive"))
      (node (ref "SW_B") (pin "1") (pinfunction "1_1") (pintype "passive"))
      (node (ref "SW_B") (pin "2") (pinfunction "2_2") (pintype "passive"))
    )
    (net (code "68") (name "Net-(R17-Pad2)") (class "Default")
      (node (ref "R17") (pin "2") (pinfunction "2_2") (pintype "passive"))
      (node (ref "SW_T") (pin "1") (pinfunction "1_1") (pintype "passive"))
      (node (ref "SW_T") (pin "2") (pinfunction "2_2") (pintype "passive"))
    )
    (net (code "69") (name "Net-(TR1-3)") (class "Default")
      (node (ref "R38") (pin "2") (pinfunction "2_2") (pintype "passive"))
      (node (ref "TR1") (pin "P3") (pinfunction "3_P3") (pintype "passive"))
    )
    (net (code "70") (name "Net-(TR2-3)") (class "Default")
      (node (ref "R34") (pin "2") (pinfunction "2_2") (pintype "passive"))
      (node (ref "TR2") (pin "P3") (pinfunction "3_P3") (pintype "passive"))
    )
    (net (code "71") (name "Net-(TR3-3)") (class "Default")
      (node (ref "R26") (pin "2") (pinfunction "2_2") (pintype "passive"))
      (node (ref "TR3") (pin "P3") (pinfunction "3_P3") (pintype "passive"))
    )
    (net (code "72") (name "Net-(TR4-3)") (class "Default")
      (node (ref "R24") (pin "2") (pinfunction "2_2") (pintype "passive"))
      (node (ref "TR4") (pin "P3") (pinfunction "3_P3") (pintype "passive"))
    )
    (net (code "73") (name "Net-(U2-EN)") (class "Default")
      (node (ref "C24") (pin "1") (pinfunction "1_1") (pintype "passive"))
      (node (ref "C25") (pin "1") (pinfunction "1_1") (pintype "passive"))
      (node (ref "L1") (pin "2") (pinfunction "2_2") (pintype "passive"))
      (node (ref "U2") (pin "1") (pinfunction "VIN_1") (pintype "input"))
      (node (ref "U2") (pin "3") (pinfunction "EN_3") (pintype "input"))
    )
    (net (code "74") (name "VCC") (class "Default")
      (node (ref "C2") (pin "+") (pinfunction "+_+") (pintype "passive"))
      (node (ref "C4") (pin "+") (pinfunction "+_+") (pintype "passive"))
      (node (ref "C7") (pin "1") (pinfunction "1_1") (pintype "passive"))
      (node (ref "C8") (pin "1") (pinfunction "1_1") (pintype "passive"))
      (node (ref "D2") (pin "C") (pinfunction "C_C") (pintype "passive"))
      (node (ref "IC1") (pin "8") (pinfunction "V+_8") (pintype "power_in"))
      (node (ref "IC2") (pin "8") (pinfunction "V+_8") (pintype "power_in"))
      (node (ref "U3") (pin "3") (pinfunction "IN_3") (pintype "input"))
    )
    (net (code "75") (name "VEE") (class "Default")
      (node (ref "C10") (pin "2") (pinfunction "2_2") (pintype "passive"))
      (node (ref "C28") (pin "1") (pinfunction "1_1") (pintype "passive"))
      (node (ref "C3") (pin "-") (pinfunction "-_-") (pintype "passive"))
      (node (ref "C9") (pin "2") (pinfunction "2_2") (pintype "passive"))
      (node (ref "D1") (pin "A") (pinfunction "A_A") (pintype "passive"))
      (node (ref "IC1") (pin "4") (pinfunction "V-_4") (pintype "power_in"))
      (node (ref "IC2") (pin "4") (pinfunction "V-_4") (pintype "power_in"))
      (node (ref "R18") (pin "1") (pinfunction "1_1") (pintype "passive"))
    )
  )
)
